# esp12carrier.net
KiCad netlist of a schematic drawn in EAGLE
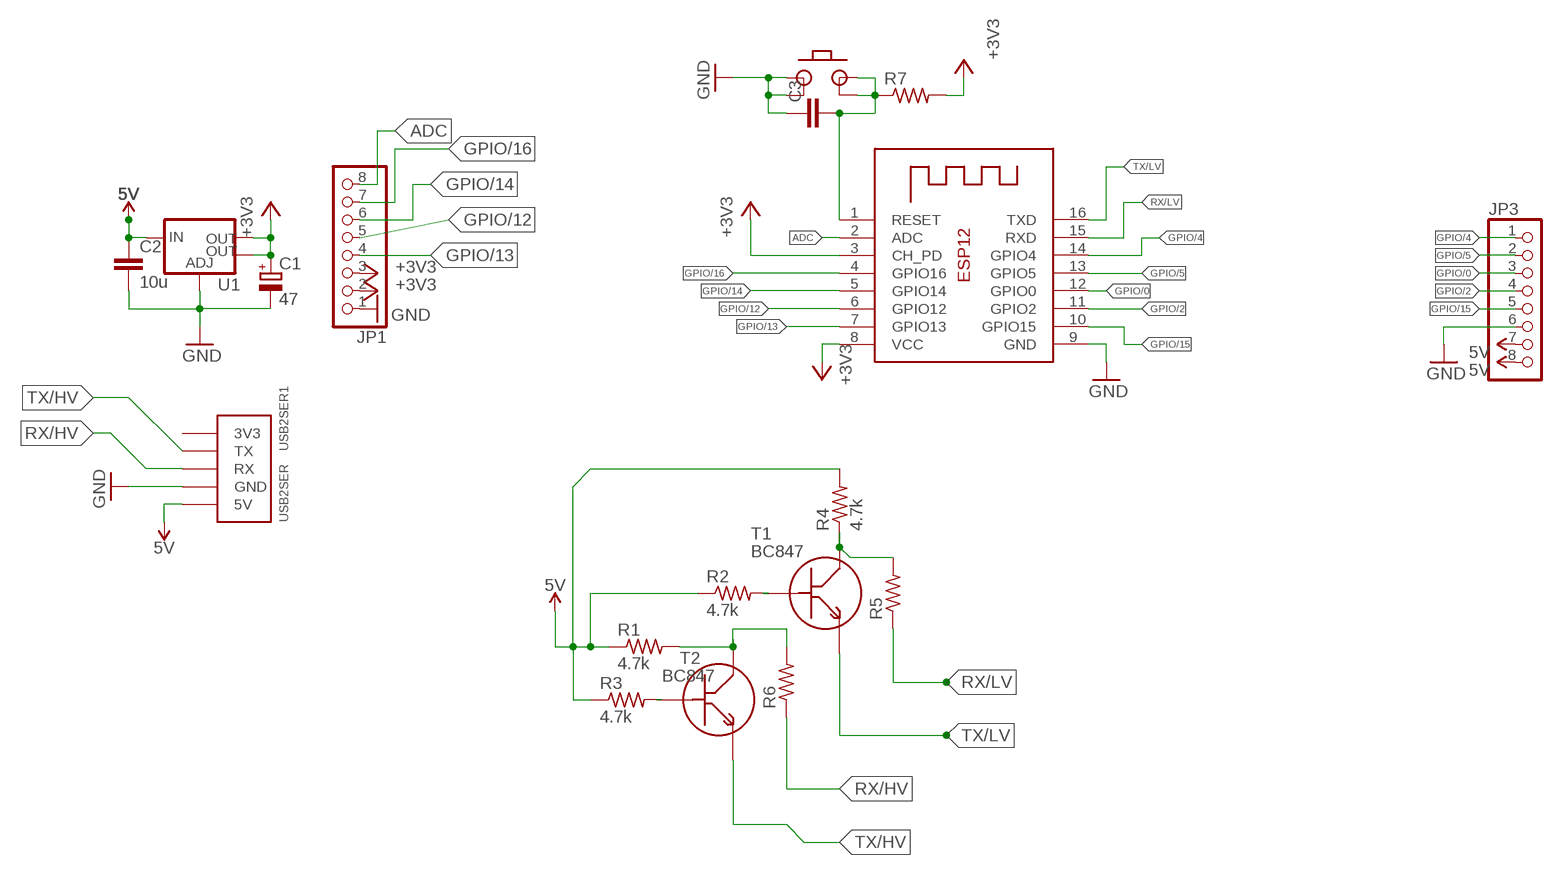
[diagram p0: schematic, sheet 1]

(export (version "E")
  (design (tool "Eeschema 10.0.6"))
  (components
    (comp (ref "C1")
      (value "47")
      (footprint "eagle-import:150CLZ-0810")
      (libsource (lib "eagle-import") (part "CPOL-EU150CLZ-0810"))
    )
    (comp (ref "C2")
      (value "10u")
      (footprint "eagle-import:C0805")
      (libsource (lib "eagle-import") (part "C-EUC0805"))
    )
    (comp (ref "C3")
      (value "C-EUC0805")
      (footprint "eagle-import:C0805")
      (libsource (lib "eagle-import") (part "C-EUC0805"))
    )
    (comp (ref "JP1")
      (value "PINHD-1X8")
      (footprint "eagle-import:1X08")
      (libsource (lib "eagle-import") (part "PINHD-1X8"))
    )
    (comp (ref "JP3")
      (value "PINHD-1X8")
      (footprint "eagle-import:1X08")
      (libsource (lib "eagle-import") (part "PINHD-1X8"))
    )
    (comp (ref "PB1")
      (value "TACTSW")
      (footprint "eagle-import:TACTSW")
      (libsource (lib "eagle-import") (part "TACTSW"))
    )
    (comp (ref "R1")
      (value "4.7k")
      (footprint "eagle-import:M0805")
      (libsource (lib "eagle-import") (part "R-US_M0805"))
    )
    (comp (ref "R2")
      (value "4.7k")
      (footprint "eagle-import:M0805")
      (libsource (lib "eagle-import") (part "R-US_M0805"))
    )
    (comp (ref "R3")
      (value "4.7k")
      (footprint "eagle-import:M0805")
      (libsource (lib "eagle-import") (part "R-US_M0805"))
    )
    (comp (ref "R4")
      (value "4.7k")
      (footprint "eagle-import:M0805")
      (libsource (lib "eagle-import") (part "R-US_M0805"))
    )
    (comp (ref "R5")
      (value "R-US_M0805")
      (footprint "eagle-import:M0805")
      (libsource (lib "eagle-import") (part "R-US_M0805"))
    )
    (comp (ref "R6")
      (value "R-US_M0805")
      (footprint "eagle-import:M0805")
      (libsource (lib "eagle-import") (part "R-US_M0805"))
    )
    (comp (ref "R7")
      (value "R-US_M0805")
      (footprint "eagle-import:M0805")
      (libsource (lib "eagle-import") (part "R-US_M0805"))
    )
    (comp (ref "T1")
      (value "BC847")
      (footprint "eagle-import:BC847")
      (libsource (lib "eagle-import") (part "BC847"))
    )
    (comp (ref "T2")
      (value "BC847")
      (footprint "eagle-import:BC847")
      (libsource (lib "eagle-import") (part "BC847"))
    )
    (comp (ref "U1")
      (value "V_REG_LM1117SOT223")
      (footprint "eagle-import:SOT223")
      (libsource (lib "eagle-import") (part "V_REG_LM1117SOT223"))
    )
    (comp (ref "USB2SER1")
      (value "USB2SER")
      (footprint "eagle-import:USB2SER")
      (libsource (lib "eagle-import") (part "USB2SER"))
    )
    (comp (ref "X2")
      (value "ESP-12")
      (footprint "eagle-import:ESP-12")
      (libsource (lib "eagle-import") (part "ESP-12"))
    )
  )
  (nets
    (net (code "1") (name "+3V3") (class "Default")
      (node (ref "C1") (pin "+") (pinfunction "+_+") (pintype "passive"))
      (node (ref "JP1") (pin "2") (pinfunction "2_2") (pintype "passive"))
      (node (ref "JP1") (pin "3") (pinfunction "3_3") (pintype "passive"))
      (node (ref "R7") (pin "2") (pinfunction "2_2") (pintype "passive"))
      (node (ref "U1") (pin "2") (pinfunction "OUT_2") (pintype "output"))
      (node (ref "U1") (pin "4") (pinfunction "OUT_4") (pintype "output"))
      (node (ref "X2") (pin "3") (pinfunction "CH_PD_3") (pintype "input"))
      (node (ref "X2") (pin "8") (pinfunction "VCC_8") (pintype "power_in"))
    )
    (net (code "2") (name "/3V3") (class "Default")
      (node (ref "USB2SER1") (pin "P$1") (pinfunction "3V3_P$1") (pintype "power_in"))
    )
    (net (code "3") (name "5V") (class "Default")
      (node (ref "C2") (pin "1") (pinfunction "1_1") (pintype "passive"))
      (node (ref "JP3") (pin "7") (pinfunction "7_7") (pintype "passive"))
      (node (ref "JP3") (pin "8") (pinfunction "8_8") (pintype "passive"))
      (node (ref "R1") (pin "1") (pinfunction "1_1") (pintype "passive"))
      (node (ref "R2") (pin "1") (pinfunction "1_1") (pintype "passive"))
      (node (ref "R3") (pin "1") (pinfunction "1_1") (pintype "passive"))
      (node (ref "R4") (pin "2") (pinfunction "2_2") (pintype "passive"))
      (node (ref "U1") (pin "3") (pinfunction "IN_3") (pintype "input"))
      (node (ref "USB2SER1") (pin "P$5") (pinfunction "5V_P$5") (pintype "power_in"))
    )
    (net (code "4") (name "ADC") (class "Default")
      (node (ref "JP1") (pin "8") (pinfunction "8_8") (pintype "passive"))
      (node (ref "X2") (pin "2") (pinfunction "ADC_2") (pintype "passive"))
    )
    (net (code "5") (name "GND") (class "Default")
      (node (ref "C1") (pin "-") (pinfunction "-_-") (pintype "passive"))
      (node (ref "C2") (pin "2") (pinfunction "2_2") (pintype "passive"))
      (node (ref "C3") (pin "1") (pinfunction "1_1") (pintype "passive"))
      (node (ref "JP1") (pin "1") (pinfunction "1_1") (pintype "passive"))
      (node (ref "JP3") (pin "6") (pinfunction "6_6") (pintype "passive"))
      (node (ref "PB1") (pin "P$1") (pinfunction "P$1_P$1") (pintype "passive"))
      (node (ref "PB1") (pin "P$2") (pinfunction "P$3_P$2") (pintype "passive"))
      (node (ref "U1") (pin "1") (pinfunction "ADJ_1") (pintype "input"))
      (node (ref "USB2SER1") (pin "P$4") (pinfunction "GND_P$4") (pintype "power_in"))
      (node (ref "X2") (pin "9") (pinfunction "GND_9") (pintype "power_in"))
    )
    (net (code "6") (name "GPIO{slash}0") (class "Default")
      (node (ref "JP3") (pin "3") (pinfunction "3_3") (pintype "passive"))
      (node (ref "X2") (pin "12") (pinfunction "GPIO0_12") (pintype "bidirectional"))
    )
    (net (code "7") (name "GPIO{slash}2") (class "Default")
      (node (ref "JP3") (pin "4") (pinfunction "4_4") (pintype "passive"))
      (node (ref "X2") (pin "11") (pinfunction "GPIO2_11") (pintype "bidirectional"))
    )
    (net (code "8") (name "GPIO{slash}4") (class "Default")
      (node (ref "JP3") (pin "1") (pinfunction "1_1") (pintype "passive"))
      (node (ref "X2") (pin "14") (pinfunction "GPIO4_14") (pintype "bidirectional"))
    )
    (net (code "9") (name "GPIO{slash}5") (class "Default")
      (node (ref "JP3") (pin "2") (pinfunction "2_2") (pintype "passive"))
      (node (ref "X2") (pin "13") (pinfunction "GPIO5_13") (pintype "bidirectional"))
    )
    (net (code "10") (name "GPIO{slash}12") (class "Default")
      (node (ref "JP1") (pin "5") (pinfunction "5_5") (pintype "passive"))
      (node (ref "X2") (pin "6") (pinfunction "GPIO12_6") (pintype "bidirectional"))
    )
    (net (code "11") (name "GPIO{slash}13") (class "Default")
      (node (ref "JP1") (pin "4") (pinfunction "4_4") (pintype "passive"))
      (node (ref "X2") (pin "7") (pinfunction "GPIO13_7") (pintype "bidirectional"))
    )
    (net (code "12") (name "GPIO{slash}14") (class "Default")
      (node (ref "JP1") (pin "6") (pinfunction "6_6") (pintype "passive"))
      (node (ref "X2") (pin "5") (pinfunction "GPIO14_5") (pintype "bidirectional"))
    )
    (net (code "13") (name "GPIO{slash}15") (class "Default")
      (node (ref "JP3") (pin "5") (pinfunction "5_5") (pintype "passive"))
      (node (ref "X2") (pin "10") (pinfunction "GPIO15_10") (pintype "bidirectional"))
    )
    (net (code "14") (name "GPIO{slash}16") (class "Default")
      (node (ref "JP1") (pin "7") (pinfunction "7_7") (pintype "passive"))
      (node (ref "X2") (pin "4") (pinfunction "GPIO16_4") (pintype "bidirectional"))
    )
    (net (code "15") (name "Net-(PB1-P$2)") (class "Default")
      (node (ref "C3") (pin "2") (pinfunction "2_2") (pintype "passive"))
      (node (ref "PB1") (pin "P$3") (pinfunction "P$2_P$3") (pintype "passive"))
      (node (ref "PB1") (pin "P$4") (pinfunction "P$4_P$4") (pintype "passive"))
      (node (ref "R7") (pin "1") (pinfunction "1_1") (pintype "passive"))
      (node (ref "X2") (pin "1") (pinfunction "RESET_1") (pintype "input"))
    )
    (net (code "16") (name "Net-(T1-B)") (class "Default")
      (node (ref "R2") (pin "2") (pinfunction "2_2") (pintype "passive"))
      (node (ref "T1") (pin "P$2") (pinfunction "B_P$2") (pintype "bidirectional"))
    )
    (net (code "17") (name "Net-(T1-C)") (class "Default")
      (node (ref "R4") (pin "1") (pinfunction "1_1") (pintype "passive"))
      (node (ref "R5") (pin "2") (pinfunction "2_2") (pintype "passive"))
      (node (ref "T1") (pin "P$1") (pinfunction "C_P$1") (pintype "bidirectional"))
    )
    (net (code "18") (name "Net-(T2-B)") (class "Default")
      (node (ref "R3") (pin "2") (pinfunction "2_2") (pintype "passive"))
      (node (ref "T2") (pin "P$2") (pinfunction "B_P$2") (pintype "bidirectional"))
    )
    (net (code "19") (name "Net-(T2-C)") (class "Default")
      (node (ref "R1") (pin "2") (pinfunction "2_2") (pintype "passive"))
      (node (ref "R6") (pin "2") (pinfunction "2_2") (pintype "passive"))
      (node (ref "T2") (pin "P$1") (pinfunction "C_P$1") (pintype "bidirectional"))
    )
    (net (code "20") (name "RX{slash}HV") (class "Default")
      (node (ref "R6") (pin "1") (pinfunction "1_1") (pintype "passive"))
      (node (ref "USB2SER1") (pin "P$3") (pinfunction "RX_P$3") (pintype "bidirectional"))
    )
    (net (code "21") (name "RX{slash}LV") (class "Default")
      (node (ref "R5") (pin "1") (pinfunction "1_1") (pintype "passive"))
      (node (ref "X2") (pin "15") (pinfunction "RXD_15") (pintype "input"))
    )
    (net (code "22") (name "TX{slash}HV") (class "Default")
      (node (ref "T2") (pin "P$3") (pinfunction "E_P$3") (pintype "bidirectional"))
      (node (ref "USB2SER1") (pin "P$2") (pinfunction "TX_P$2") (pintype "bidirectional"))
    )
    (net (code "23") (name "TX{slash}LV") (class "Default")
      (node (ref "T1") (pin "P$3") (pinfunction "E_P$3") (pintype "bidirectional"))
      (node (ref "X2") (pin "16") (pinfunction "TXD_16") (pintype "output"))
    )
  )
)
